# MCUPinout.net
KiCad netlist of a schematic drawn in Altium Designer
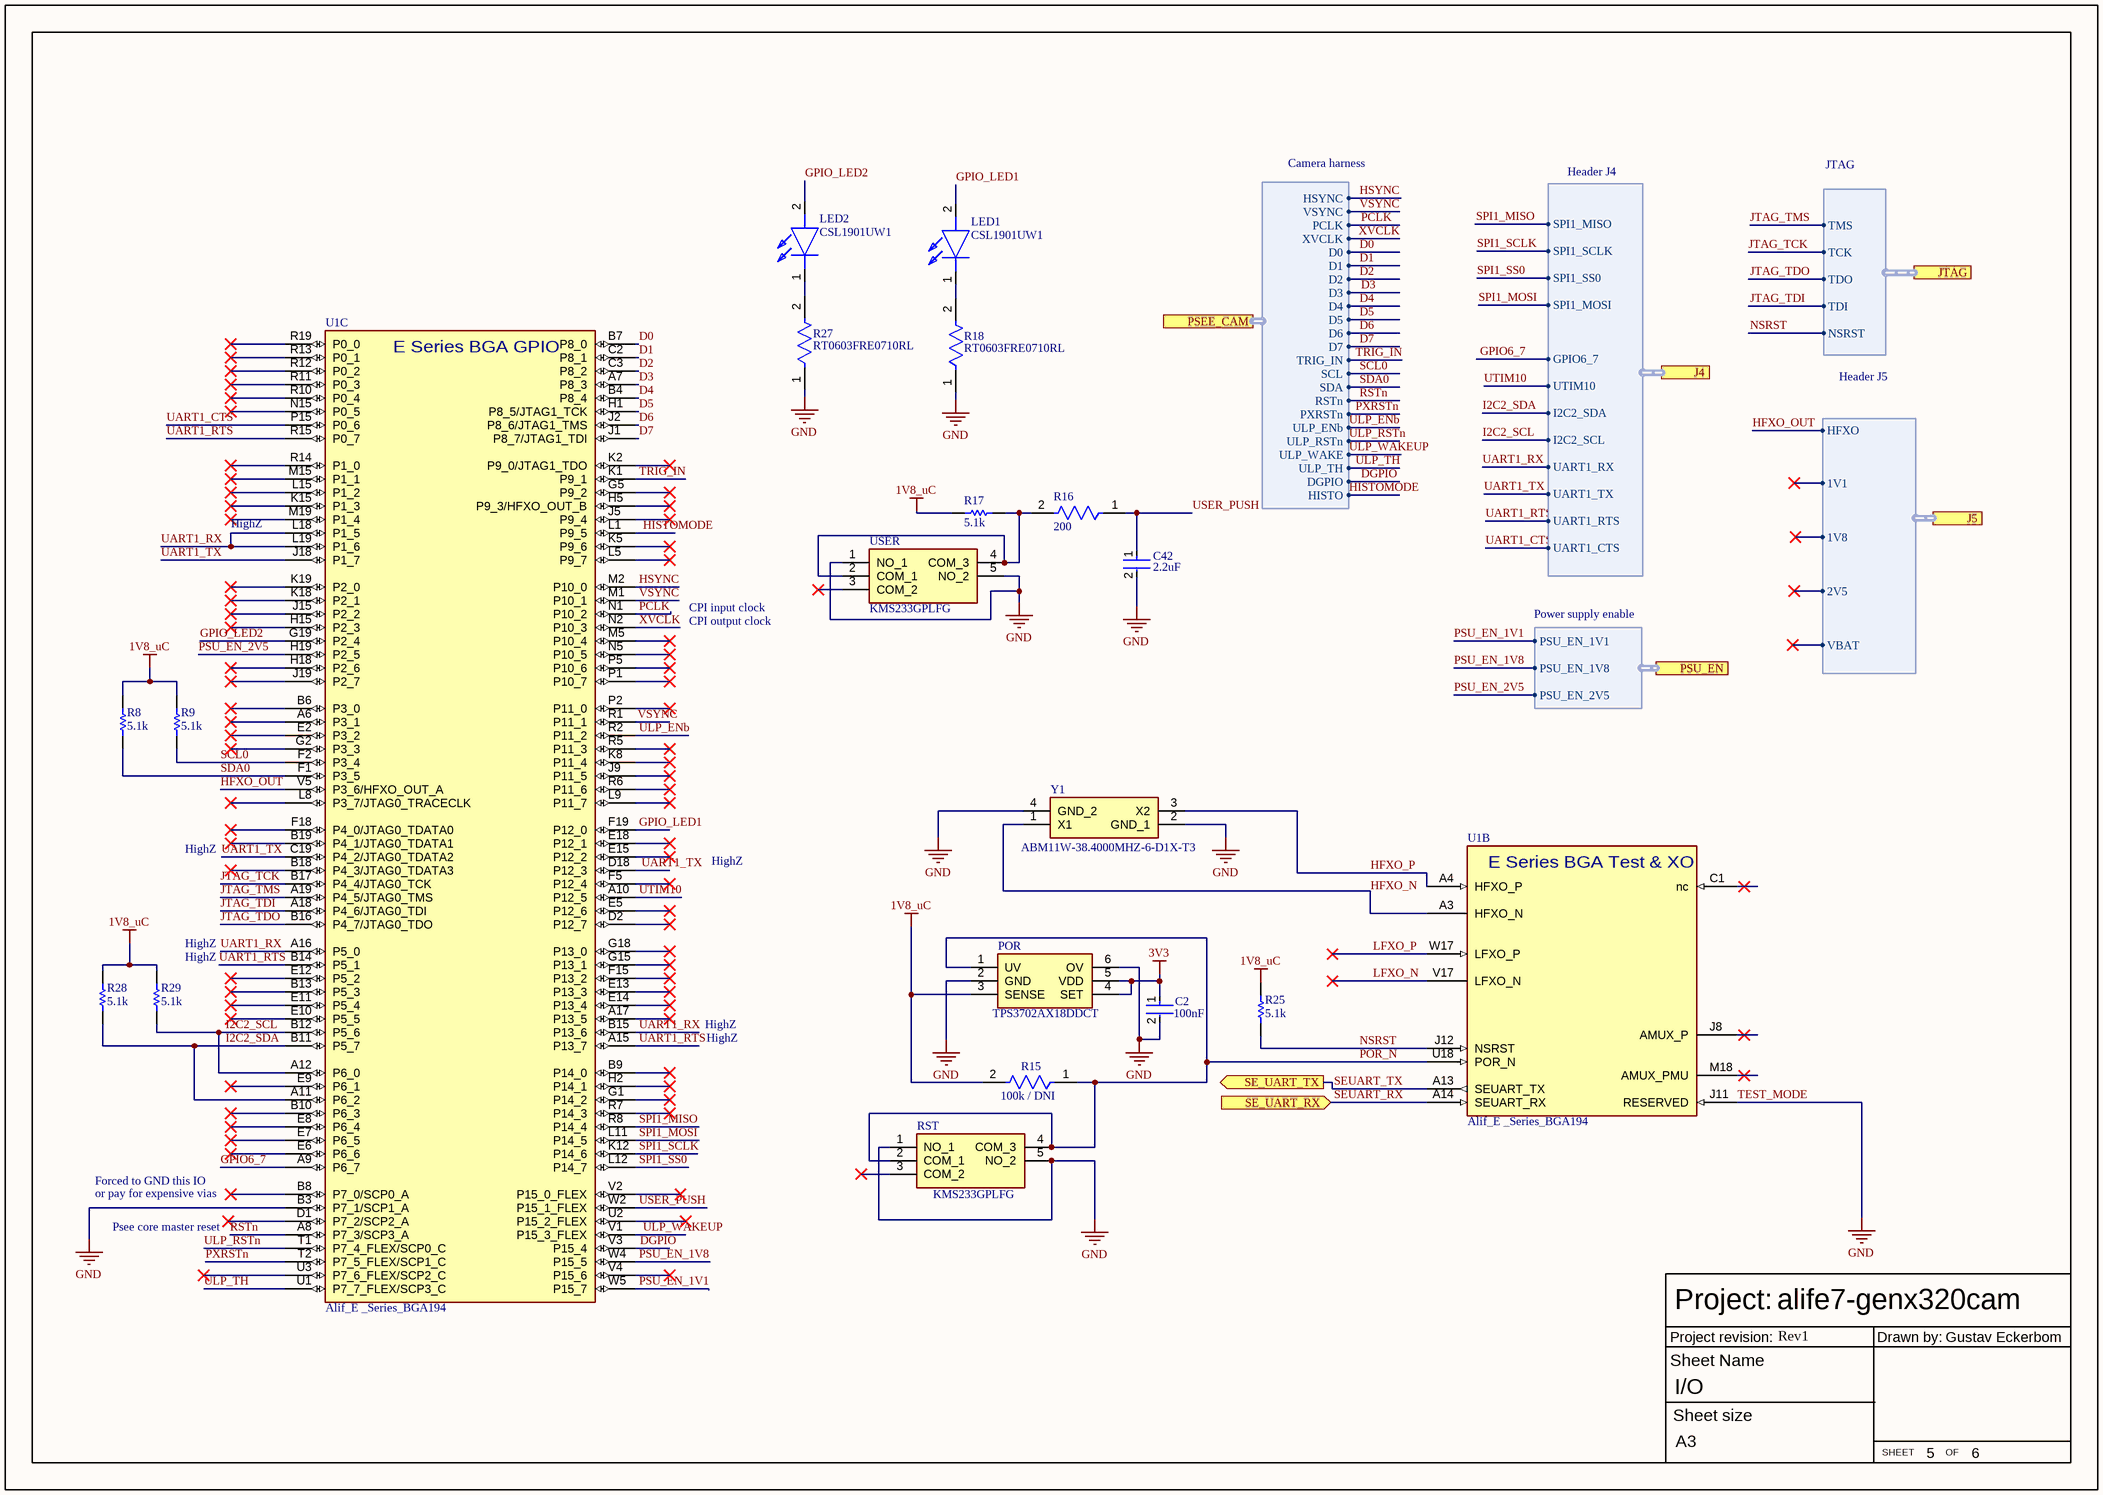
[diagram p0: MCUPinout.SchDoc]

(export (version "E")
  (design (tool "Eeschema 10.0.6"))
  (components
    (comp (ref "C2")
      (value "100nF")
      (footprint "FP-C0603X104K3RACTU-MFG")
      (description "CAP CER 0.1UF 25V X7R 0603")
      (fields (field (name "VOLTAGE") "25V") (field (name "TOLERANCE") "10%"))
      (libsource (lib "Altium Content Vault") (part "02cd4be3c70576c341d710602a673aa"))
    )
    (comp (ref "C42")
      (value "2.2uF")
      (footprint "FP-CC0603-DA-MFG")
      (description "CAP CER 2.2UF 6.3V X5R 0603")
      (fields (field (name "TOLERANCE") "0.1") (field (name "MANUFACTURER") "YAGEO"))
      (libsource (lib "Altium Content Vault") (part "11868f565c42a9108669ba33697ecf6"))
    )
    (comp (ref "LED1")
      (value "CSL1901UW1")
      (footprint "SamacSys:CSL1901UW1")
      (description "LED")
      (fields (field (name "MOUSER PART NUMBER") "755-CSL1901UW1"))
      (libsource (lib "SamacSys") (part "CSL1901UW1"))
    )
    (comp (ref "LED2")
      (value "CSL1901UW1")
      (footprint "SamacSys:CSL1901UW1")
      (description "LED")
      (fields (field (name "MOUSER PART NUMBER") "755-CSL1901UW1"))
      (libsource (lib "SamacSys") (part "CSL1901UW1"))
    )
    (comp (ref "POR")
      (value "TPS3702AX18DDCT")
      (footprint "SamacSys:SOT95P280X110-6N")
      (description "Integrated Circuit")
      (fields (field (name "MOUSER PART NUMBER") "595-TPS3702AX18DDCT"))
      (libsource (lib "SamacSys") (part "TPS3702AX18DDCT"))
    )
    (comp (ref "R8")
      (value "5.1k")
      (footprint "RESC1608X55X30LL15T15")
      (fields (field (name "PART NUMBER") "ERJ-3GEYJ512V") (field (name "MANUFACTURER") "Panasonic"))
      (libsource (lib "Altium Content Vault") (part "RES"))
    )
    (comp (ref "R9")
      (value "5.1k")
      (footprint "RESC1608X55X30LL15T15")
      (fields (field (name "PART NUMBER") "ERJ-3GEYJ512V") (field (name "MANUFACTURER") "Panasonic"))
      (libsource (lib "Altium Content Vault") (part "RES"))
    )
    (comp (ref "R15")
      (value "100k / DNI")
      (footprint "FP-RC0603-0_55-IPC_B")
      (description "RES 100K OHM 1% 1/10W 0603")
      (fields (field (name "TOLERANCE") "1%"))
      (libsource (lib "Altium Content Vault") (part "1029c3af85768c4190bb7ad29bc67b5"))
    )
    (comp (ref "R16")
      (value "200")
      (footprint "FP-MCR03-IPC_C")
      (fields (field (name "POWER") "100mW") (field (name "TOLERANCE") "5%") (field (name "Comment") "200R"))
      (libsource (lib "Gustav Eckerbom") (part "1029c3af85768c4190bb7ad29bc67b5"))
    )
    (comp (ref "R17")
      (value "5.1k")
      (footprint "RESC1608X55X30LL15T15")
      (fields (field (name "PART NUMBER") "ERJ-3GEYJ512V") (field (name "MANUFACTURER") "Panasonic"))
      (libsource (lib "Altium Content Vault") (part "RES"))
    )
    (comp (ref "R18")
      (value "RT0603FRE0710RL")
      (footprint "FP-RT0603-IPC_C")
      (description "RES SMD 10 OHM 1% 1/10W 0603")
      (fields (field (name "MANUFACTURER") "Yageo") (field (name "TOLERANCE") "0.01"))
      (libsource (lib "Altium Content Vault") (part "1029c3af85768c4190bb7ad29bc67b5"))
    )
    (comp (ref "R25")
      (value "5.1k")
      (footprint "RESC1608X55X30LL15T15")
      (fields (field (name "PART NUMBER") "ERJ-3GEYJ512V") (field (name "MANUFACTURER") "Panasonic"))
      (libsource (lib "Altium Content Vault") (part "RES"))
    )
    (comp (ref "R27")
      (value "RT0603FRE0710RL")
      (footprint "FP-RT0603-IPC_C")
      (description "RES SMD 10 OHM 1% 1/10W 0603")
      (fields (field (name "MANUFACTURER") "Yageo") (field (name "TOLERANCE") "0.01"))
      (libsource (lib "Altium Content Vault") (part "1029c3af85768c4190bb7ad29bc67b5"))
    )
    (comp (ref "R28")
      (value "5.1k")
      (footprint "RESC1608X55X30LL15T15")
      (fields (field (name "PART NUMBER") "ERJ-3GEYJ512V") (field (name "MANUFACTURER") "Panasonic"))
      (libsource (lib "Altium Content Vault") (part "RES"))
    )
    (comp (ref "R29")
      (value "5.1k")
      (footprint "RESC1608X55X30LL15T15")
      (fields (field (name "PART NUMBER") "ERJ-3GEYJ512V") (field (name "MANUFACTURER") "Panasonic"))
      (libsource (lib "Altium Content Vault") (part "RES"))
    )
    (comp (ref "RST")
      (value "KMS233GPLFG")
      (footprint "SamacSys:KMS233GPLFG")
      (description "Switch")
      (fields (field (name "MOUSER PART NUMBER") "611-KMS233GPLFG"))
      (libsource (lib "SamacSys") (part "KMS233GPLFG"))
    )
    (comp (ref "U1")
      (value "Alif_E _Series_BGA194")
      (footprint "BGA194 _CENTERED")
      (description "IC,Alif E7 MCU, Rev B silicon,BGA194")
      (libsource (lib "AlifSoC") (part "E7_B0_194BGA"))
    )
    (comp (ref "USER")
      (value "KMS233GPLFG")
      (footprint "SamacSys:KMS233GPLFG")
      (description "Switch")
      (fields (field (name "MOUSER PART NUMBER") "611-KMS233GPLFG"))
      (libsource (lib "SamacSys") (part "KMS233GPLFG"))
    )
    (comp (ref "Y1")
      (value "ABM11W-38.4000MHZ-6-D1X-T3")
      (footprint "SamacSys:ABM11W300000MHZ4B1UT3")
      (description "Crystal or Oscillator")
      (fields (field (name "MOUSER PART NUMBER") "815-11W38.4-6D1XT"))
      (libsource (lib "*") (part "ABM11W-38.4000MHZ-6-D1X-T3"))
    )
  )
  (nets
    (net (code "10") (name "/D0") (class "Default")
      (node (ref "U1") (pin "B7") (pinfunction "P8_0_B7") (pintype "bidirectional"))
    )
    (net (code "11") (name "/D1") (class "Default")
      (node (ref "U1") (pin "C2") (pinfunction "P8_1_C2") (pintype "bidirectional"))
    )
    (net (code "12") (name "/D2") (class "Default")
      (node (ref "U1") (pin "C3") (pinfunction "P8_2_C3") (pintype "bidirectional"))
    )
    (net (code "13") (name "/D3") (class "Default")
      (node (ref "U1") (pin "A7") (pinfunction "P8_3_A7") (pintype "bidirectional"))
    )
    (net (code "14") (name "/D4") (class "Default")
      (node (ref "U1") (pin "B4") (pinfunction "P8_4_B4") (pintype "bidirectional"))
    )
    (net (code "15") (name "/D5") (class "Default")
      (node (ref "U1") (pin "H1") (pinfunction "P8_5/JTAG1_TCK_H1") (pintype "bidirectional"))
    )
    (net (code "16") (name "/D6") (class "Default")
      (node (ref "U1") (pin "J2") (pinfunction "P8_6/JTAG1_TMS_J2") (pintype "bidirectional"))
    )
    (net (code "17") (name "/D7") (class "Default")
      (node (ref "U1") (pin "J1") (pinfunction "P8_7/JTAG1_TDI_J1") (pintype "bidirectional"))
    )
    (net (code "18") (name "/DGPIO") (class "Default")
      (node (ref "U1") (pin "V3") (pinfunction "P15_4_V3") (pintype "bidirectional"))
    )
    (net (code "19") (name "/GPIO6_7") (class "Default")
      (node (ref "U1") (pin "A9") (pinfunction "P6_7_A9") (pintype "bidirectional"))
    )
    (net (code "20") (name "/GPIO_LED1") (class "Default")
      (node (ref "LED1") (pin "2") (pinfunction "A_2") (pintype "passive"))
      (node (ref "U1") (pin "F19") (pinfunction "P12_0_F19") (pintype "bidirectional"))
    )
    (net (code "21") (name "/GPIO_LED2") (class "Default")
      (node (ref "LED2") (pin "2") (pinfunction "A_2") (pintype "passive"))
      (node (ref "U1") (pin "G19") (pinfunction "P2_4_G19") (pintype "bidirectional"))
    )
    (net (code "22") (name "/HFXO_N") (class "Default")
      (node (ref "U1") (pin "A3") (pinfunction "HFXO_N_A3") (pintype "passive"))
      (node (ref "Y1") (pin "1") (pinfunction "X1_1") (pintype "passive"))
    )
    (net (code "23") (name "/HFXO_OUT") (class "Default")
      (node (ref "U1") (pin "V5") (pinfunction "P3_6/HFXO_OUT_A_V5") (pintype "bidirectional"))
    )
    (net (code "24") (name "/HFXO_P") (class "Default")
      (node (ref "U1") (pin "A4") (pinfunction "HFXO_P_A4") (pintype "input"))
      (node (ref "Y1") (pin "3") (pinfunction "X2_3") (pintype "passive"))
    )
    (net (code "25") (name "/HISTOMODE") (class "Default")
      (node (ref "U1") (pin "L1") (pinfunction "P9_5_L1") (pintype "bidirectional"))
    )
    (net (code "26") (name "/HSYNC") (class "Default")
      (node (ref "U1") (pin "M2") (pinfunction "P10_0_M2") (pintype "bidirectional"))
    )
    (net (code "27") (name "/I2C2_SCL") (class "Default")
      (node (ref "R29") (pin "1") (pinfunction "1_1") (pintype "passive"))
      (node (ref "U1") (pin "A12") (pinfunction "P6_0_A12") (pintype "bidirectional"))
      (node (ref "U1") (pin "B12") (pinfunction "P5_6_B12") (pintype "bidirectional"))
    )
    (net (code "28") (name "/I2C2_SDA") (class "Default")
      (node (ref "R28") (pin "1") (pinfunction "1_1") (pintype "passive"))
      (node (ref "U1") (pin "A11") (pinfunction "P6_2_A11") (pintype "bidirectional"))
      (node (ref "U1") (pin "B11") (pinfunction "P5_7_B11") (pintype "bidirectional"))
    )
    (net (code "29") (name "/JTAG_TCK") (class "Default")
      (node (ref "U1") (pin "B17") (pinfunction "P4_4/JTAG0_TCK_B17") (pintype "bidirectional"))
    )
    (net (code "30") (name "/JTAG_TDI") (class "Default")
      (node (ref "U1") (pin "A18") (pinfunction "P4_6/JTAG0_TDI_A18") (pintype "bidirectional"))
    )
    (net (code "31") (name "/JTAG_TDO") (class "Default")
      (node (ref "U1") (pin "B16") (pinfunction "P4_7/JTAG0_TDO_B16") (pintype "bidirectional"))
    )
    (net (code "32") (name "/JTAG_TMS") (class "Default")
      (node (ref "U1") (pin "A19") (pinfunction "P4_5/JTAG0_TMS_A19") (pintype "bidirectional"))
    )
    (net (code "33") (name "/LFXO_N") (class "Default")
      (node (ref "U1") (pin "V17") (pinfunction "LFXO_N_V17") (pintype "passive+no_connect"))
    )
    (net (code "34") (name "/LFXO_P") (class "Default")
      (node (ref "U1") (pin "W17") (pinfunction "LFXO_P_W17") (pintype "input+no_connect"))
    )
    (net (code "35") (name "/NSRST") (class "Default")
      (node (ref "R25") (pin "2") (pinfunction "2_2") (pintype "passive"))
      (node (ref "U1") (pin "J12") (pinfunction "NSRST_J12") (pintype "input"))
    )
    (net (code "36") (name "/PCLK") (class "Default")
      (node (ref "U1") (pin "N1") (pinfunction "P10_2_N1") (pintype "bidirectional"))
    )
    (net (code "37") (name "/POR_N") (class "Default")
      (node (ref "POR") (pin "1") (pinfunction "UV_1") (pintype "passive"))
      (node (ref "R15") (pin "1") (pinfunction "1_1") (pintype "passive"))
      (node (ref "RST") (pin "2") (pinfunction "COM_1_2") (pintype "passive"))
      (node (ref "RST") (pin "4") (pinfunction "COM_3_4") (pintype "passive"))
      (node (ref "U1") (pin "U18") (pinfunction "POR_N_U18") (pintype "input"))
    )
    (net (code "38") (name "/PSU_EN_1V1") (class "Default")
      (node (ref "U1") (pin "W5") (pinfunction "P15_7_W5") (pintype "bidirectional"))
    )
    (net (code "39") (name "/PSU_EN_1V8") (class "Default")
      (node (ref "U1") (pin "W4") (pinfunction "P15_5_W4") (pintype "bidirectional"))
    )
    (net (code "40") (name "/PSU_EN_2V5") (class "Default")
      (node (ref "U1") (pin "H19") (pinfunction "P2_5_H19") (pintype "bidirectional"))
    )
    (net (code "41") (name "/PXRSTn") (class "Default")
      (node (ref "U1") (pin "T2") (pinfunction "P7_5_FLEX/SCP1_C_T2") (pintype "bidirectional"))
    )
    (net (code "42") (name "/RSTn") (class "Default")
      (node (ref "U1") (pin "A8") (pinfunction "P7_3/SCP3_A_A8") (pintype "bidirectional"))
    )
    (net (code "43") (name "/SCL0") (class "Default")
      (node (ref "R9") (pin "1") (pinfunction "1_1") (pintype "passive"))
      (node (ref "U1") (pin "F2") (pinfunction "P3_4_F2") (pintype "bidirectional"))
    )
    (net (code "44") (name "/SDA0") (class "Default")
      (node (ref "R8") (pin "1") (pinfunction "1_1") (pintype "passive"))
      (node (ref "U1") (pin "F1") (pinfunction "P3_5_F1") (pintype "bidirectional"))
    )
    (net (code "45") (name "/SEUART_RX") (class "Default")
      (node (ref "U1") (pin "A14") (pinfunction "SEUART_RX_A14") (pintype "input"))
    )
    (net (code "46") (name "/SEUART_TX") (class "Default")
      (node (ref "U1") (pin "A13") (pinfunction "SEUART_TX_A13") (pintype "output"))
    )
    (net (code "47") (name "/SPI1_MISO") (class "Default")
      (node (ref "U1") (pin "R8") (pinfunction "P14_4_R8") (pintype "bidirectional"))
    )
    (net (code "48") (name "/SPI1_MOSI") (class "Default")
      (node (ref "U1") (pin "L11") (pinfunction "P14_5_L11") (pintype "bidirectional"))
    )
    (net (code "49") (name "/SPI1_SCLK") (class "Default")
      (node (ref "U1") (pin "K12") (pinfunction "P14_6_K12") (pintype "bidirectional"))
    )
    (net (code "50") (name "/SPI1_SS0") (class "Default")
      (node (ref "U1") (pin "L12") (pinfunction "P14_7_L12") (pintype "bidirectional"))
    )
    (net (code "51") (name "/TRIG_IN") (class "Default")
      (node (ref "U1") (pin "K1") (pinfunction "P9_1_K1") (pintype "bidirectional"))
    )
    (net (code "52") (name "/UART1_CTS") (class "Default")
      (node (ref "U1") (pin "P15") (pinfunction "P0_6_P15") (pintype "bidirectional"))
    )
    (net (code "53") (name "/UART1_RTS") (class "Default")
      (node (ref "U1") (pin "A15") (pinfunction "P13_7_A15") (pintype "bidirectional"))
      (node (ref "U1") (pin "B14") (pinfunction "P5_1_B14") (pintype "bidirectional"))
      (node (ref "U1") (pin "R15") (pinfunction "P0_7_R15") (pintype "bidirectional"))
    )
    (net (code "54") (name "/UART1_RX") (class "Default")
      (node (ref "U1") (pin "A16") (pinfunction "P5_0_A16") (pintype "bidirectional"))
      (node (ref "U1") (pin "B15") (pinfunction "P13_6_B15") (pintype "bidirectional"))
      (node (ref "U1") (pin "L18") (pinfunction "P1_5_L18") (pintype "bidirectional"))
      (node (ref "U1") (pin "L19") (pinfunction "P1_6_L19") (pintype "bidirectional"))
    )
    (net (code "55") (name "/UART1_TX") (class "Default")
      (node (ref "U1") (pin "C19") (pinfunction "P4_2/JTAG0_TDATA2_C19") (pintype "bidirectional"))
      (node (ref "U1") (pin "D18") (pinfunction "P12_3_D18") (pintype "bidirectional"))
      (node (ref "U1") (pin "J18") (pinfunction "P1_7_J18") (pintype "bidirectional"))
    )
    (net (code "56") (name "/ULP_ENb") (class "Default")
      (node (ref "U1") (pin "R2") (pinfunction "P11_2_R2") (pintype "bidirectional"))
    )
    (net (code "57") (name "/ULP_RSTn") (class "Default")
      (node (ref "U1") (pin "T1") (pinfunction "P7_4_FLEX/SCP0_C_T1") (pintype "bidirectional"))
    )
    (net (code "58") (name "/ULP_TH") (class "Default")
      (node (ref "U1") (pin "U1") (pinfunction "P7_7_FLEX/SCP3_C_U1") (pintype "bidirectional"))
    )
    (net (code "59") (name "/ULP_WAKEUP") (class "Default")
      (node (ref "U1") (pin "V1") (pinfunction "P15_3_FLEX_V1") (pintype "bidirectional"))
    )
    (net (code "60") (name "/USER_PUSH") (class "Default")
      (node (ref "C42") (pin "1") (pinfunction "1_1") (pintype "passive"))
      (node (ref "R16") (pin "1") (pinfunction "1_1") (pintype "passive"))
      (node (ref "U1") (pin "W2") (pinfunction "P15_1_FLEX_W2") (pintype "bidirectional"))
    )
    (net (code "61") (name "/UTIM10") (class "Default")
      (node (ref "U1") (pin "A10") (pinfunction "P12_5_A10") (pintype "bidirectional"))
    )
    (net (code "62") (name "/VSYNC") (class "Default")
      (node (ref "U1") (pin "M1") (pinfunction "P10_1_M1") (pintype "bidirectional"))
      (node (ref "U1") (pin "R1") (pinfunction "P11_1_R1") (pintype "bidirectional"))
    )
    (net (code "63") (name "/XVCLK") (class "Default")
      (node (ref "U1") (pin "N2") (pinfunction "P10_3_N2") (pintype "bidirectional"))
    )
    (net (code "69") (name "1V8_uC") (class "Default")
      (node (ref "POR") (pin "3") (pinfunction "SENSE_3") (pintype "passive"))
      (node (ref "R15") (pin "2") (pinfunction "2_2") (pintype "passive"))
      (node (ref "R17") (pin "2") (pinfunction "2_2") (pintype "passive"))
      (node (ref "R25") (pin "1") (pinfunction "1_1") (pintype "passive"))
      (node (ref "R28") (pin "2") (pinfunction "2_2") (pintype "passive"))
      (node (ref "R29") (pin "2") (pinfunction "2_2") (pintype "passive"))
      (node (ref "R8") (pin "2") (pinfunction "2_2") (pintype "passive"))
      (node (ref "R9") (pin "2") (pinfunction "2_2") (pintype "passive"))
    )
    (net (code "70") (name "3V3") (class "Default")
      (node (ref "C2") (pin "1") (pinfunction "1_1") (pintype "passive"))
      (node (ref "POR") (pin "4") (pinfunction "SET_4") (pintype "passive"))
      (node (ref "POR") (pin "5") (pinfunction "VDD_5") (pintype "passive"))
    )
    (net (code "71") (name "GND") (class "Default")
      (node (ref "C2") (pin "2") (pinfunction "2_2") (pintype "passive"))
      (node (ref "C42") (pin "2") (pinfunction "2_2") (pintype "passive"))
      (node (ref "POR") (pin "2") (pinfunction "GND_2") (pintype "passive"))
      (node (ref "POR") (pin "6") (pinfunction "OV_6") (pintype "passive"))
      (node (ref "R18") (pin "1") (pinfunction "1_1") (pintype "passive"))
      (node (ref "R27") (pin "1") (pinfunction "1_1") (pintype "passive"))
      (node (ref "RST") (pin "1") (pinfunction "NO_1_1") (pintype "passive"))
      (node (ref "RST") (pin "5") (pinfunction "NO_2_5") (pintype "passive"))
      (node (ref "U1") (pin "B3") (pinfunction "P7_1/SCP1_A_B3") (pintype "bidirectional"))
      (node (ref "U1") (pin "J11") (pinfunction "RESERVED_J11") (pintype "input"))
      (node (ref "USER") (pin "1") (pinfunction "NO_1_1") (pintype "passive"))
      (node (ref "USER") (pin "5") (pinfunction "NO_2_5") (pintype "passive"))
      (node (ref "Y1") (pin "2") (pinfunction "GND_1_2") (pintype "passive"))
      (node (ref "Y1") (pin "4") (pinfunction "GND_2_4") (pintype "passive"))
    )
    (net (code "72") (name "Net-(LED1-K)") (class "Default")
      (node (ref "LED1") (pin "1") (pinfunction "K_1") (pintype "passive"))
      (node (ref "R18") (pin "2") (pinfunction "2_2") (pintype "passive"))
    )
    (net (code "73") (name "Net-(LED2-K)") (class "Default")
      (node (ref "LED2") (pin "1") (pinfunction "K_1") (pintype "passive"))
      (node (ref "R27") (pin "2") (pinfunction "2_2") (pintype "passive"))
    )
    (net (code "74") (name "Net-(USER-COM_1)") (class "Default")
      (node (ref "R16") (pin "2") (pinfunction "2_2") (pintype "passive"))
      (node (ref "R17") (pin "1") (pinfunction "1_1") (pintype "passive"))
      (node (ref "USER") (pin "2") (pinfunction "COM_1_2") (pintype "passive"))
      (node (ref "USER") (pin "4") (pinfunction "COM_3_4") (pintype "passive"))
    )
    (net (code "75") (name "unconnected-(RST-COM_2-Pad3)") (class "Default")
      (node (ref "RST") (pin "3") (pinfunction "COM_2_3") (pintype "passive+no_connect"))
    )
    (net (code "76") (name "unconnected-(U1B-AMUX_P-PadJ8)") (class "Default")
      (node (ref "U1") (pin "J8") (pinfunction "AMUX_P_J8") (pintype "passive"))
    )
    (net (code "77") (name "unconnected-(U1B-AMUX_PMU-PadM18)") (class "Default")
      (node (ref "U1") (pin "M18") (pinfunction "AMUX_PMU_M18") (pintype "passive"))
    )
    (net (code "78") (name "unconnected-(U1B-nc-PadC1)") (class "Default")
      (node (ref "U1") (pin "C1") (pinfunction "nc_C1") (pintype "input"))
    )
    (net (code "79") (name "unconnected-(U1C-P0_0-PadR19)") (class "Default")
      (node (ref "U1") (pin "R19") (pinfunction "P0_0_R19") (pintype "bidirectional+no_connect"))
    )
    (net (code "80") (name "unconnected-(U1C-P0_1-PadR13)") (class "Default")
      (node (ref "U1") (pin "R13") (pinfunction "P0_1_R13") (pintype "bidirectional+no_connect"))
    )
    (net (code "81") (name "unconnected-(U1C-P0_2-PadR12)") (class "Default")
      (node (ref "U1") (pin "R12") (pinfunction "P0_2_R12") (pintype "bidirectional+no_connect"))
    )
    (net (code "82") (name "unconnected-(U1C-P0_3-PadR11)") (class "Default")
      (node (ref "U1") (pin "R11") (pinfunction "P0_3_R11") (pintype "bidirectional+no_connect"))
    )
    (net (code "83") (name "unconnected-(U1C-P0_4-PadR10)") (class "Default")
      (node (ref "U1") (pin "R10") (pinfunction "P0_4_R10") (pintype "bidirectional+no_connect"))
    )
    (net (code "84") (name "unconnected-(U1C-P0_5-PadN15)") (class "Default")
      (node (ref "U1") (pin "N15") (pinfunction "P0_5_N15") (pintype "bidirectional+no_connect"))
    )
    (net (code "85") (name "unconnected-(U1C-P1_0-PadR14)") (class "Default")
      (node (ref "U1") (pin "R14") (pinfunction "P1_0_R14") (pintype "bidirectional+no_connect"))
    )
    (net (code "86") (name "unconnected-(U1C-P1_1-PadM15)") (class "Default")
      (node (ref "U1") (pin "M15") (pinfunction "P1_1_M15") (pintype "bidirectional+no_connect"))
    )
    (net (code "87") (name "unconnected-(U1C-P1_2-PadL15)") (class "Default")
      (node (ref "U1") (pin "L15") (pinfunction "P1_2_L15") (pintype "bidirectional+no_connect"))
    )
    (net (code "88") (name "unconnected-(U1C-P1_3-PadK15)") (class "Default")
      (node (ref "U1") (pin "K15") (pinfunction "P1_3_K15") (pintype "bidirectional+no_connect"))
    )
    (net (code "89") (name "unconnected-(U1C-P1_4-PadM19)") (class "Default")
      (node (ref "U1") (pin "M19") (pinfunction "P1_4_M19") (pintype "bidirectional+no_connect"))
    )
    (net (code "90") (name "unconnected-(U1C-P2_0-PadK19)") (class "Default")
      (node (ref "U1") (pin "K19") (pinfunction "P2_0_K19") (pintype "bidirectional+no_connect"))
    )
    (net (code "91") (name "unconnected-(U1C-P2_1-PadK18)") (class "Default")
      (node (ref "U1") (pin "K18") (pinfunction "P2_1_K18") (pintype "bidirectional+no_connect"))
    )
    (net (code "92") (name "unconnected-(U1C-P2_2-PadJ15)") (class "Default")
      (node (ref "U1") (pin "J15") (pinfunction "P2_2_J15") (pintype "bidirectional+no_connect"))
    )
    (net (code "93") (name "unconnected-(U1C-P2_3-PadH15)") (class "Default")
      (node (ref "U1") (pin "H15") (pinfunction "P2_3_H15") (pintype "bidirectional+no_connect"))
    )
    (net (code "94") (name "unconnected-(U1C-P2_6-PadH18)") (class "Default")
      (node (ref "U1") (pin "H18") (pinfunction "P2_6_H18") (pintype "bidirectional+no_connect"))
    )
    (net (code "95") (name "unconnected-(U1C-P2_7-PadJ19)") (class "Default")
      (node (ref "U1") (pin "J19") (pinfunction "P2_7_J19") (pintype "bidirectional+no_connect"))
    )
    (net (code "96") (name "unconnected-(U1C-P3_0-PadB6)") (class "Default")
      (node (ref "U1") (pin "B6") (pinfunction "P3_0_B6") (pintype "bidirectional+no_connect"))
    )
    (net (code "97") (name "unconnected-(U1C-P3_1-PadA6)") (class "Default")
      (node (ref "U1") (pin "A6") (pinfunction "P3_1_A6") (pintype "bidirectional+no_connect"))
    )
    (net (code "98") (name "unconnected-(U1C-P3_2-PadE2)") (class "Default")
      (node (ref "U1") (pin "E2") (pinfunction "P3_2_E2") (pintype "bidirectional+no_connect"))
    )
    (net (code "99") (name "unconnected-(U1C-P3_3-PadG2)") (class "Default")
      (node (ref "U1") (pin "G2") (pinfunction "P3_3_G2") (pintype "bidirectional+no_connect"))
    )
    (net (code "100") (name "unconnected-(U1C-P3_7{slash}JTAG0_TRACECLK-PadL8)") (class "Default")
      (node (ref "U1") (pin "L8") (pinfunction "P3_7/JTAG0_TRACECLK_L8") (pintype "bidirectional+no_connect"))
    )
    (net (code "101") (name "unconnected-(U1C-P4_0{slash}JTAG0_TDATA0-PadF18)") (class "Default")
      (node (ref "U1") (pin "F18") (pinfunction "P4_0/JTAG0_TDATA0_F18") (pintype "bidirectional+no_connect"))
    )
    (net (code "102") (name "unconnected-(U1C-P4_1{slash}JTAG0_TDATA1-PadB19)") (class "Default")
      (node (ref "U1") (pin "B19") (pinfunction "P4_1/JTAG0_TDATA1_B19") (pintype "bidirectional+no_connect"))
    )
    (net (code "103") (name "unconnected-(U1C-P4_3{slash}JTAG0_TDATA3-PadB18)") (class "Default")
      (node (ref "U1") (pin "B18") (pinfunction "P4_3/JTAG0_TDATA3_B18") (pintype "bidirectional+no_connect"))
    )
    (net (code "104") (name "unconnected-(U1C-P5_2-PadE12)") (class "Default")
      (node (ref "U1") (pin "E12") (pinfunction "P5_2_E12") (pintype "bidirectional+no_connect"))
    )
    (net (code "105") (name "unconnected-(U1C-P5_3-PadB13)") (class "Default")
      (node (ref "U1") (pin "B13") (pinfunction "P5_3_B13") (pintype "bidirectional+no_connect"))
    )
    (net (code "106") (name "unconnected-(U1C-P5_4-PadE11)") (class "Default")
      (node (ref "U1") (pin "E11") (pinfunction "P5_4_E11") (pintype "bidirectional+no_connect"))
    )
    (net (code "107") (name "unconnected-(U1C-P5_5-PadE10)") (class "Default")
      (node (ref "U1") (pin "E10") (pinfunction "P5_5_E10") (pintype "bidirectional+no_connect"))
    )
    (net (code "108") (name "unconnected-(U1C-P6_1-PadE9)") (class "Default")
      (node (ref "U1") (pin "E9") (pinfunction "P6_1_E9") (pintype "bidirectional+no_connect"))
    )
    (net (code "109") (name "unconnected-(U1C-P6_3-PadB10)") (class "Default")
      (node (ref "U1") (pin "B10") (pinfunction "P6_3_B10") (pintype "bidirectional+no_connect"))
    )
    (net (code "110") (name "unconnected-(U1C-P6_4-PadE8)") (class "Default")
      (node (ref "U1") (pin "E8") (pinfunction "P6_4_E8") (pintype "bidirectional+no_connect"))
    )
    (net (code "111") (name "unconnected-(U1C-P6_5-PadE7)") (class "Default")
      (node (ref "U1") (pin "E7") (pinfunction "P6_5_E7") (pintype "bidirectional+no_connect"))
    )
    (net (code "112") (name "unconnected-(U1C-P6_6-PadE6)") (class "Default")
      (node (ref "U1") (pin "E6") (pinfunction "P6_6_E6") (pintype "bidirectional+no_connect"))
    )
    (net (code "113") (name "unconnected-(U1C-P7_0{slash}SCP0_A-PadB8)") (class "Default")
      (node (ref "U1") (pin "B8") (pinfunction "P7_0/SCP0_A_B8") (pintype "bidirectional+no_connect"))
    )
    (net (code "114") (name "unconnected-(U1C-P7_2{slash}SCP2_A-PadD1)") (class "Default")
      (node (ref "U1") (pin "D1") (pinfunction "P7_2/SCP2_A_D1") (pintype "bidirectional+no_connect"))
    )
    (net (code "115") (name "unconnected-(U1C-P7_6_FLEX{slash}SCP2_C-PadU3)") (class "Default")
      (node (ref "U1") (pin "U3") (pinfunction "P7_6_FLEX/SCP2_C_U3") (pintype "bidirectional+no_connect"))
    )
    (net (code "116") (name "unconnected-(U1C-P9_0{slash}JTAG1_TDO-PadK2)") (class "Default")
      (node (ref "U1") (pin "K2") (pinfunction "P9_0/JTAG1_TDO_K2") (pintype "bidirectional+no_connect"))
    )
    (net (code "117") (name "unconnected-(U1C-P9_2-PadG5)") (class "Default")
      (node (ref "U1") (pin "G5") (pinfunction "P9_2_G5") (pintype "bidirectional+no_connect"))
    )
    (net (code "118") (name "unconnected-(U1C-P9_3{slash}HFXO_OUT_B-PadH5)") (class "Default")
      (node (ref "U1") (pin "H5") (pinfunction "P9_3/HFXO_OUT_B_H5") (pintype "bidirectional+no_connect"))
    )
    (net (code "119") (name "unconnected-(U1C-P9_4-PadJ5)") (class "Default")
      (node (ref "U1") (pin "J5") (pinfunction "P9_4_J5") (pintype "bidirectional+no_connect"))
    )
    (net (code "120") (name "unconnected-(U1C-P9_6-PadK5)") (class "Default")
      (node (ref "U1") (pin "K5") (pinfunction "P9_6_K5") (pintype "bidirectional+no_connect"))
    )
    (net (code "121") (name "unconnected-(U1C-P9_7-PadL5)") (class "Default")
      (node (ref "U1") (pin "L5") (pinfunction "P9_7_L5") (pintype "bidirectional+no_connect"))
    )
    (net (code "122") (name "unconnected-(U1C-P10_4-PadM5)") (class "Default")
      (node (ref "U1") (pin "M5") (pinfunction "P10_4_M5") (pintype "bidirectional+no_connect"))
    )
    (net (code "123") (name "unconnected-(U1C-P10_5-PadN5)") (class "Default")
      (node (ref "U1") (pin "N5") (pinfunction "P10_5_N5") (pintype "bidirectional+no_connect"))
    )
    (net (code "124") (name "unconnected-(U1C-P10_6-PadP5)") (class "Default")
      (node (ref "U1") (pin "P5") (pinfunction "P10_6_P5") (pintype "bidirectional+no_connect"))
    )
    (net (code "125") (name "unconnected-(U1C-P10_7-PadP1)") (class "Default")
      (node (ref "U1") (pin "P1") (pinfunction "P10_7_P1") (pintype "bidirectional+no_connect"))
    )
    (net (code "126") (name "unconnected-(U1C-P11_0-PadP2)") (class "Default")
      (node (ref "U1") (pin "P2") (pinfunction "P11_0_P2") (pintype "bidirectional+no_connect"))
    )
    (net (code "127") (name "unconnected-(U1C-P11_3-PadR5)") (class "Default")
      (node (ref "U1") (pin "R5") (pinfunction "P11_3_R5") (pintype "bidirectional+no_connect"))
    )
    (net (code "128") (name "unconnected-(U1C-P11_4-PadK8)") (class "Default")
      (node (ref "U1") (pin "K8") (pinfunction "P11_4_K8") (pintype "bidirectional+no_connect"))
    )
    (net (code "129") (name "unconnected-(U1C-P11_5-PadJ9)") (class "Default")
      (node (ref "U1") (pin "J9") (pinfunction "P11_5_J9") (pintype "bidirectional+no_connect"))
    )
    (net (code "130") (name "unconnected-(U1C-P11_6-PadR6)") (class "Default")
      (node (ref "U1") (pin "R6") (pinfunction "P11_6_R6") (pintype "bidirectional+no_connect"))
    )
    (net (code "131") (name "unconnected-(U1C-P11_7-PadL9)") (class "Default")
      (node (ref "U1") (pin "L9") (pinfunction "P11_7_L9") (pintype "bidirectional+no_connect"))
    )
    (net (code "132") (name "unconnected-(U1C-P12_1-PadE18)") (class "Default")
      (node (ref "U1") (pin "E18") (pinfunction "P12_1_E18") (pintype "bidirectional+no_connect"))
    )
    (net (code "133") (name "unconnected-(U1C-P12_2-PadE15)") (class "Default")
      (node (ref "U1") (pin "E15") (pinfunction "P12_2_E15") (pintype "bidirectional+no_connect"))
    )
    (net (code "134") (name "unconnected-(U1C-P12_4-PadF5)") (class "Default")
      (node (ref "U1") (pin "F5") (pinfunction "P12_4_F5") (pintype "bidirectional+no_connect"))
    )
    (net (code "135") (name "unconnected-(U1C-P12_6-PadE5)") (class "Default")
      (node (ref "U1") (pin "E5") (pinfunction "P12_6_E5") (pintype "bidirectional+no_connect"))
    )
    (net (code "136") (name "unconnected-(U1C-P12_7-PadD2)") (class "Default")
      (node (ref "U1") (pin "D2") (pinfunction "P12_7_D2") (pintype "bidirectional+no_connect"))
    )
    (net (code "137") (name "unconnected-(U1C-P13_0-PadG18)") (class "Default")
      (node (ref "U1") (pin "G18") (pinfunction "P13_0_G18") (pintype "bidirectional+no_connect"))
    )
    (net (code "138") (name "unconnected-(U1C-P13_1-PadG15)") (class "Default")
      (node (ref "U1") (pin "G15") (pinfunction "P13_1_G15") (pintype "bidirectional+no_connect"))
    )
    (net (code "139") (name "unconnected-(U1C-P13_2-PadF15)") (class "Default")
      (node (ref "U1") (pin "F15") (pinfunction "P13_2_F15") (pintype "bidirectional+no_connect"))
    )
    (net (code "140") (name "unconnected-(U1C-P13_3-PadE13)") (class "Default")
      (node (ref "U1") (pin "E13") (pinfunction "P13_3_E13") (pintype "bidirectional+no_connect"))
    )
    (net (code "141") (name "unconnected-(U1C-P13_4-PadE14)") (class "Default")
      (node (ref "U1") (pin "E14") (pinfunction "P13_4_E14") (pintype "bidirectional+no_connect"))
    )
    (net (code "142") (name "unconnected-(U1C-P13_5-PadA17)") (class "Default")
      (node (ref "U1") (pin "A17") (pinfunction "P13_5_A17") (pintype "bidirectional+no_connect"))
    )
    (net (code "143") (name "unconnected-(U1C-P14_0-PadB9)") (class "Default")
      (node (ref "U1") (pin "B9") (pinfunction "P14_0_B9") (pintype "bidirectional+no_connect"))
    )
    (net (code "144") (name "unconnected-(U1C-P14_1-PadH2)") (class "Default")
      (node (ref "U1") (pin "H2") (pinfunction "P14_1_H2") (pintype "bidirectional+no_connect"))
    )
    (net (code "145") (name "unconnected-(U1C-P14_2-PadG1)") (class "Default")
      (node (ref "U1") (pin "G1") (pinfunction "P14_2_G1") (pintype "bidirectional+no_connect"))
    )
    (net (code "146") (name "unconnected-(U1C-P14_3-PadR7)") (class "Default")
      (node (ref "U1") (pin "R7") (pinfunction "P14_3_R7") (pintype "bidirectional+no_connect"))
    )
    (net (code "147") (name "unconnected-(U1C-P15_0_FLEX-PadV2)") (class "Default")
      (node (ref "U1") (pin "V2") (pinfunction "P15_0_FLEX_V2") (pintype "bidirectional+no_connect"))
    )
    (net (code "148") (name "unconnected-(U1C-P15_2_FLEX-PadU2)") (class "Default")
      (node (ref "U1") (pin "U2") (pinfunction "P15_2_FLEX_U2") (pintype "bidirectional+no_connect"))
    )
    (net (code "149") (name "unconnected-(U1C-P15_6-PadV4)") (class "Default")
      (node (ref "U1") (pin "V4") (pinfunction "P15_6_V4") (pintype "bidirectional+no_connect"))
    )
    (net (code "150") (name "unconnected-(USER-COM_2-Pad3)") (class "Default")
      (node (ref "USER") (pin "3") (pinfunction "COM_2_3") (pintype "passive+no_connect"))
    )
  )
)
